# UserInterface.net
KiCad netlist of a schematic drawn in Altium Designer
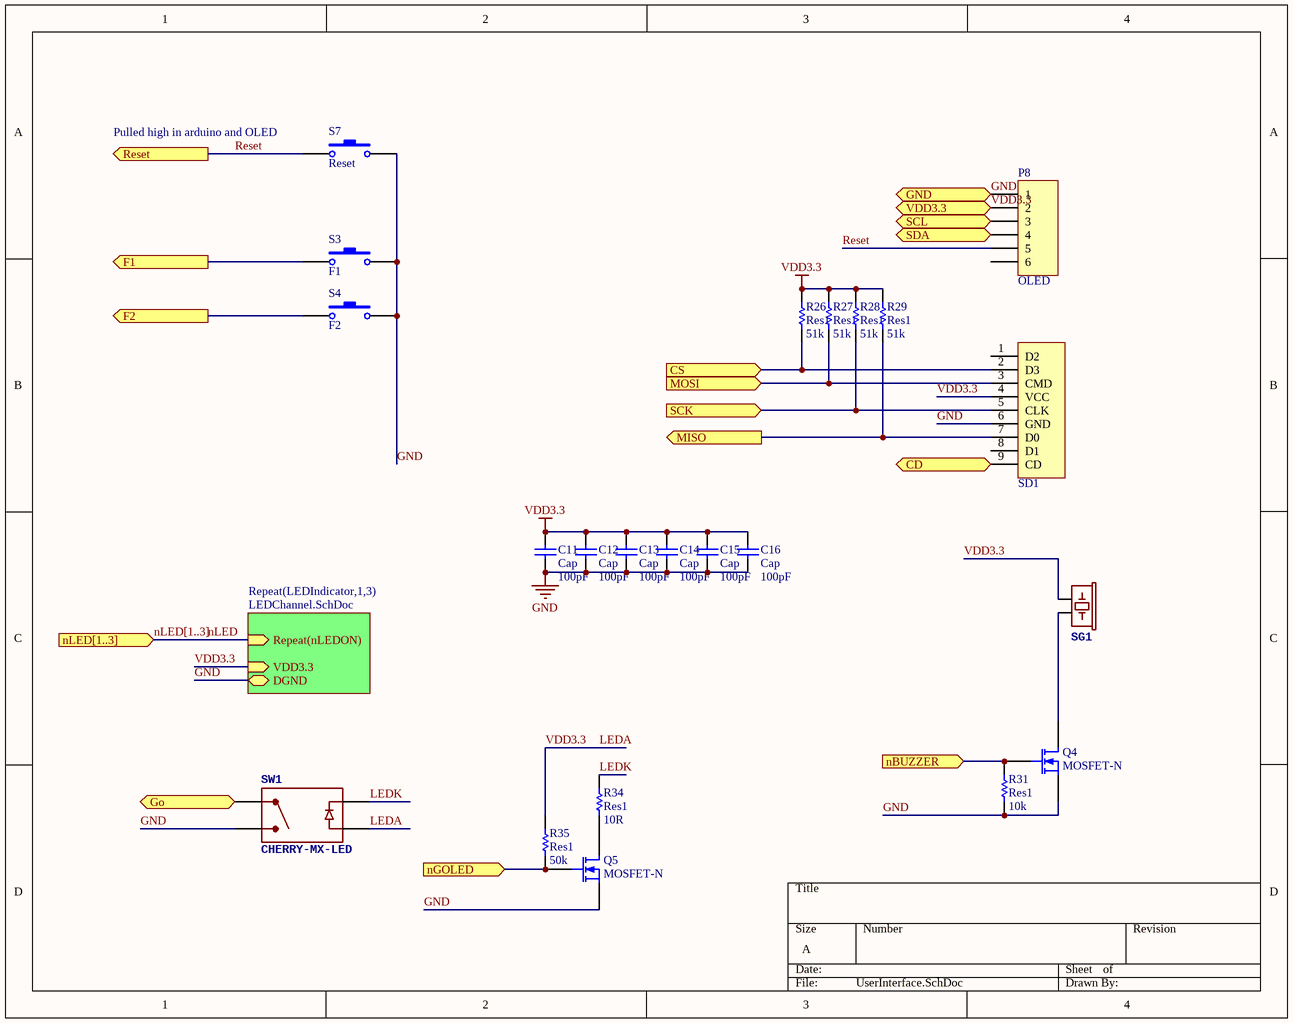
[diagram p0: UserInterface.SchDoc]

(export (version "E")
  (design (tool "Eeschema 10.0.6"))
  (components
    (comp (ref "C11")
      (value "Cap")
      (footprint "CAP_0805")
      (description "Capacitor")
      (fields (field (name "ALTIUM_VALUE") "100pF") (field (name "PUBLISHER") "Altium Limited"))
      (libsource (lib "Miscellaneous Devices") (part "Cap"))
    )
    (comp (ref "C12")
      (value "Cap")
      (footprint "CAP_0805")
      (description "Capacitor")
      (fields (field (name "ALTIUM_VALUE") "100pF") (field (name "PUBLISHER") "Altium Limited"))
      (libsource (lib "Miscellaneous Devices") (part "Cap"))
    )
    (comp (ref "C13")
      (value "Cap")
      (footprint "CAP_0805")
      (description "Capacitor")
      (fields (field (name "ALTIUM_VALUE") "100pF") (field (name "PUBLISHER") "Altium Limited"))
      (libsource (lib "Miscellaneous Devices") (part "Cap"))
    )
    (comp (ref "C14")
      (value "Cap")
      (footprint "CAP_0805")
      (description "Capacitor")
      (fields (field (name "ALTIUM_VALUE") "100pF") (field (name "PUBLISHER") "Altium Limited"))
      (libsource (lib "Miscellaneous Devices") (part "Cap"))
    )
    (comp (ref "C15")
      (value "Cap")
      (footprint "CAP_0805")
      (description "Capacitor")
      (fields (field (name "ALTIUM_VALUE") "100pF") (field (name "PUBLISHER") "Altium Limited"))
      (libsource (lib "Miscellaneous Devices") (part "Cap"))
    )
    (comp (ref "C16")
      (value "Cap")
      (footprint "CAP_0805")
      (description "Capacitor")
      (fields (field (name "ALTIUM_VALUE") "100pF") (field (name "PUBLISHER") "Altium Limited"))
      (libsource (lib "Miscellaneous Devices") (part "Cap"))
    )
    (comp (ref "P8")
      (value "OLED")
      (footprint "OLEd")
      (description "Header, 6-Pin")
      (fields (field (name "PUBLISHER") "Altium Limited"))
      (libsource (lib "Miscellaneous Connectors") (part "Header 6"))
    )
    (comp (ref "Q4")
      (value "MOSFET-N")
      (footprint "SOT23-3")
      (description "N-Channel MOSFET")
      (fields (field (name "PUBLISHER") "Altium Limited"))
      (libsource (lib "Miscellaneous Devices") (part "MOSFET-N"))
    )
    (comp (ref "Q5")
      (value "MOSFET-N")
      (footprint "SOT23-3")
      (description "N-Channel MOSFET")
      (fields (field (name "PUBLISHER") "Altium Limited"))
      (libsource (lib "Miscellaneous Devices") (part "MOSFET-N"))
    )
    (comp (ref "R26")
      (value "Res1")
      (footprint "RES_0805")
      (description "Resistor")
      (fields (field (name "ALTIUM_VALUE") "51k") (field (name "PUBLISHER") "Altium Limited"))
      (libsource (lib "SmartMouse2016") (part "Res1"))
    )
    (comp (ref "R27")
      (value "Res1")
      (footprint "RES_0805")
      (description "Resistor")
      (fields (field (name "ALTIUM_VALUE") "51k") (field (name "PUBLISHER") "Altium Limited"))
      (libsource (lib "SmartMouse2016") (part "Res1"))
    )
    (comp (ref "R28")
      (value "Res1")
      (footprint "RES_0805")
      (description "Resistor")
      (fields (field (name "ALTIUM_VALUE") "51k") (field (name "PUBLISHER") "Altium Limited"))
      (libsource (lib "SmartMouse2016") (part "Res1"))
    )
    (comp (ref "R29")
      (value "Res1")
      (footprint "RES_0805")
      (description "Resistor")
      (fields (field (name "ALTIUM_VALUE") "51k") (field (name "PUBLISHER") "Altium Limited"))
      (libsource (lib "SmartMouse2016") (part "Res1"))
    )
    (comp (ref "R31")
      (value "Res1")
      (footprint "RES_0805")
      (description "Resistor")
      (fields (field (name "ALTIUM_VALUE") "10k") (field (name "PUBLISHER") "Altium Limited"))
      (libsource (lib "Miscellaneous Devices") (part "Res1"))
    )
    (comp (ref "R34")
      (value "Res1")
      (footprint "RES_0805")
      (description "Resistor")
      (fields (field (name "ALTIUM_VALUE") "10R") (field (name "PUBLISHER") "Altium Limited"))
      (libsource (lib "Miscellaneous Devices") (part "Res1"))
    )
    (comp (ref "R35")
      (value "Res1")
      (footprint "RES_0805")
      (description "Resistor")
      (fields (field (name "ALTIUM_VALUE") "50k") (field (name "PUBLISHER") "Altium Limited"))
      (libsource (lib "Miscellaneous Devices") (part "Res1"))
    )
    (comp (ref "S3")
      (value "F1")
      (footprint "ButtonTACT_3x6x2.5_180")
      (description "Switch")
      (fields (field (name "PUBLISHER") "Altium Limited"))
      (libsource (lib "Miscellaneous Devices") (part "SW-PB"))
    )
    (comp (ref "S4")
      (value "F2")
      (footprint "ButtonTACT_3x6x2.5_180")
      (description "Switch")
      (fields (field (name "PUBLISHER") "Altium Limited"))
      (libsource (lib "Miscellaneous Devices") (part "SW-PB"))
    )
    (comp (ref "S7")
      (value "Reset")
      (footprint "ButtonTACT_3x6x2.5_180")
      (description "Switch")
      (fields (field (name "PUBLISHER") "Altium Limited"))
      (libsource (lib "Miscellaneous Devices") (part "SW-PB"))
    )
    (comp (ref "SD1")
      (value "SD_Card_TF")
      (footprint "PCB_SDCard:SD_Card_TF")
      (description "SD")
      (libsource (lib "SCH_SDCard") (part "SD_Card_TF"))
    )
    (comp (ref "SG1")
      (value "Buzzer 12mmSpark Fun Electronics SKU : Comp-Buzzer")
      (footprint "Buzzer_5x5")
      (libsource (lib "SparkFun-Electromechanical") (part "BUZZERPTH"))
    )
    (comp (ref "SW1")
      (value "CHERRY-MX-LED")
      (footprint "MX-LED")
      (libsource (lib "cherry-switches") (part "CHERRY-MX-LED"))
    )
  )
  (nets
    (net (code "4") (name "/CD") (class "Default")
      (node (ref "SD1") (pin "9") (pinfunction "CD_9") (pintype "passive"))
    )
    (net (code "5") (name "/CS") (class "Default")
      (node (ref "R26") (pin "1") (pinfunction "1_1") (pintype "passive"))
      (node (ref "SD1") (pin "2") (pinfunction "D3_2") (pintype "passive"))
    )
    (net (code "6") (name "/F1") (class "Default")
      (node (ref "S3") (pin "1") (pinfunction "1_1") (pintype "passive"))
    )
    (net (code "7") (name "/F2") (class "Default")
      (node (ref "S4") (pin "1") (pinfunction "1_1") (pintype "passive"))
    )
    (net (code "8") (name "/Go") (class "Default")
      (node (ref "SW1") (pin "P$1") (pinfunction "1_P$1") (pintype "passive"))
    )
    (net (code "9") (name "/LEDK") (class "Default")
      (node (ref "R34") (pin "2") (pinfunction "2_2") (pintype "passive"))
      (node (ref "SW1") (pin "P$3") (pinfunction "P$3_P$3") (pintype "passive"))
    )
    (net (code "10") (name "/MISO") (class "Default")
      (node (ref "R29") (pin "1") (pinfunction "1_1") (pintype "passive"))
      (node (ref "SD1") (pin "7") (pinfunction "D0_7") (pintype "passive"))
    )
    (net (code "11") (name "/MOSI") (class "Default")
      (node (ref "R27") (pin "1") (pinfunction "1_1") (pintype "passive"))
      (node (ref "SD1") (pin "3") (pinfunction "CMD_3") (pintype "passive"))
    )
    (net (code "12") (name "/Reset") (class "Default")
      (node (ref "P8") (pin "5") (pinfunction "5_5") (pintype "passive"))
      (node (ref "S7") (pin "1") (pinfunction "1_1") (pintype "passive"))
    )
    (net (code "13") (name "/SCK") (class "Default")
      (node (ref "R28") (pin "1") (pinfunction "1_1") (pintype "passive"))
      (node (ref "SD1") (pin "5") (pinfunction "CLK_5") (pintype "passive"))
    )
    (net (code "14") (name "/SCL") (class "Default")
      (node (ref "P8") (pin "3") (pinfunction "3_3") (pintype "passive"))
    )
    (net (code "15") (name "/SDA") (class "Default")
      (node (ref "P8") (pin "4") (pinfunction "4_4") (pintype "passive"))
    )
    (net (code "16") (name "/nBUZZER") (class "Default")
      (node (ref "Q4") (pin "2") (pinfunction "G_2") (pintype "passive"))
      (node (ref "R31") (pin "2") (pinfunction "2_2") (pintype "passive"))
    )
    (net (code "17") (name "/nGOLED") (class "Default")
      (node (ref "Q5") (pin "2") (pinfunction "G_2") (pintype "passive"))
      (node (ref "R35") (pin "1") (pinfunction "1_1") (pintype "passive"))
    )
    (net (code "20") (name "GND") (class "Default")
      (node (ref "C11") (pin "1") (pinfunction "1_1") (pintype "passive"))
      (node (ref "C12") (pin "1") (pinfunction "1_1") (pintype "passive"))
      (node (ref "C13") (pin "1") (pinfunction "1_1") (pintype "passive"))
      (node (ref "C14") (pin "1") (pinfunction "1_1") (pintype "passive"))
      (node (ref "C15") (pin "1") (pinfunction "1_1") (pintype "passive"))
      (node (ref "C16") (pin "1") (pinfunction "1_1") (pintype "passive"))
      (node (ref "P8") (pin "1") (pinfunction "1_1") (pintype "passive"))
      (node (ref "Q4") (pin "3") (pinfunction "S_3") (pintype "passive"))
      (node (ref "Q5") (pin "3") (pinfunction "S_3") (pintype "passive"))
      (node (ref "R31") (pin "1") (pinfunction "1_1") (pintype "passive"))
      (node (ref "S3") (pin "2") (pinfunction "2_2") (pintype "passive"))
      (node (ref "S4") (pin "2") (pinfunction "2_2") (pintype "passive"))
      (node (ref "S7") (pin "2") (pinfunction "2_2") (pintype "passive"))
      (node (ref "SD1") (pin "6") (pinfunction "GND_6") (pintype "passive"))
      (node (ref "SW1") (pin "P$2") (pinfunction "2_P$2") (pintype "passive"))
    )
    (net (code "21") (name "Net-(Q4-D)") (class "Default")
      (node (ref "Q4") (pin "1") (pinfunction "D_1") (pintype "passive"))
      (node (ref "SG1") (pin "-") (pinfunction "2_-") (pintype "passive"))
    )
    (net (code "22") (name "Net-(Q5-D)") (class "Default")
      (node (ref "Q5") (pin "1") (pinfunction "D_1") (pintype "passive"))
      (node (ref "R34") (pin "1") (pinfunction "1_1") (pintype "passive"))
    )
    (net (code "23") (name "VDD3.3") (class "Default")
      (node (ref "C11") (pin "2") (pinfunction "2_2") (pintype "passive"))
      (node (ref "C12") (pin "2") (pinfunction "2_2") (pintype "passive"))
      (node (ref "C13") (pin "2") (pinfunction "2_2") (pintype "passive"))
      (node (ref "C14") (pin "2") (pinfunction "2_2") (pintype "passive"))
      (node (ref "C15") (pin "2") (pinfunction "2_2") (pintype "passive"))
      (node (ref "C16") (pin "2") (pinfunction "2_2") (pintype "passive"))
      (node (ref "P8") (pin "2") (pinfunction "2_2") (pintype "passive"))
      (node (ref "R26") (pin "2") (pinfunction "2_2") (pintype "passive"))
      (node (ref "R27") (pin "2") (pinfunction "2_2") (pintype "passive"))
      (node (ref "R28") (pin "2") (pinfunction "2_2") (pintype "passive"))
      (node (ref "R29") (pin "2") (pinfunction "2_2") (pintype "passive"))
      (node (ref "R35") (pin "2") (pinfunction "2_2") (pintype "passive"))
      (node (ref "SD1") (pin "4") (pinfunction "VCC_4") (pintype "passive"))
      (node (ref "SG1") (pin "+") (pinfunction "1_+") (pintype "passive"))
      (node (ref "SW1") (pin "P$4") (pinfunction "P$4_P$4") (pintype "passive"))
    )
    (net (code "24") (name "unconnected-(P8-Pad6)") (class "Default")
      (node (ref "P8") (pin "6") (pinfunction "6_6") (pintype "passive"))
    )
    (net (code "25") (name "unconnected-(SD1-D1-Pad8)") (class "Default")
      (node (ref "SD1") (pin "8") (pinfunction "D1_8") (pintype "passive"))
    )
    (net (code "26") (name "unconnected-(SD1-D2-Pad1)") (class "Default")
      (node (ref "SD1") (pin "1") (pinfunction "D2_1") (pintype "passive"))
    )
  )
)
